# RTU_B2_Power_Supply_Buck_Boost_Regulator.net
KiCad netlist of a schematic drawn in Altium Designer
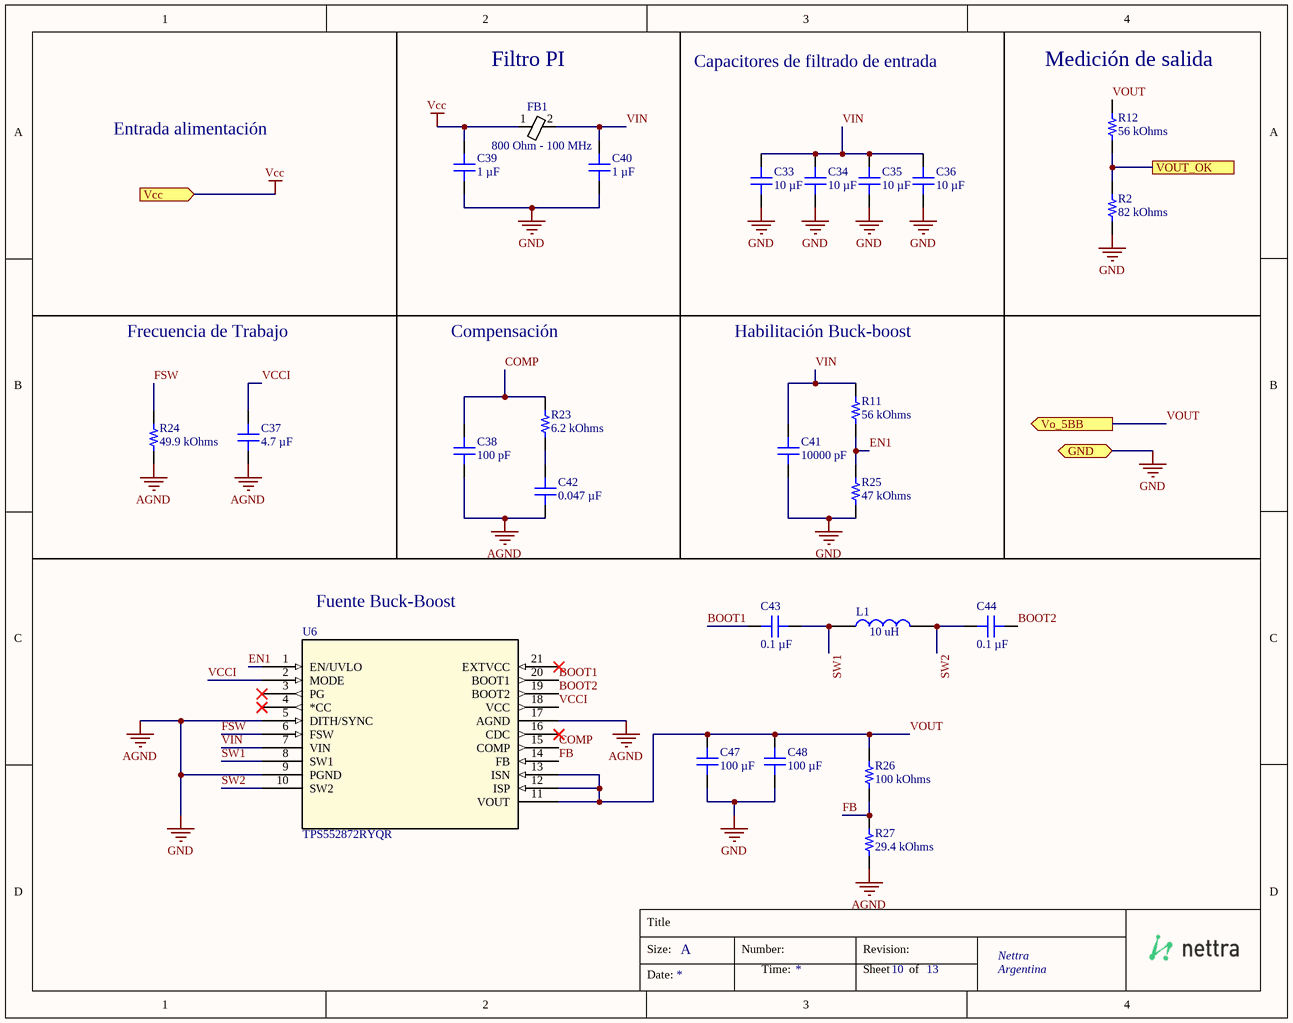
[diagram p0: RTU_B2_Power_Supply_Buck_Boost_Regulator.SchDoc]

(export (version "E")
  (design (tool "Eeschema 10.0.6"))
  (components
    (comp (ref "C33")
      (value "10 µF")
      (footprint "CAP 1210_3225 - 1MM")
      (description "CAP CER 10UF 50V X7S 1210")
      (fields
        (field (name "PART NUMBER") "GCJ32EC71H106KA01L")
        (field (name "MANUFACTURER") "Murata Electronics")
      )
      (libsource (lib "Celestial Altium Library - altium_library") (part "Capacitor"))
    )
    (comp (ref "C34")
      (value "10 µF")
      (footprint "CAP 1210_3225 - 1MM")
      (description "CAP CER 10UF 50V X7S 1210")
      (fields
        (field (name "PART NUMBER") "GCJ32EC71H106KA01L")
        (field (name "MANUFACTURER") "Murata Electronics")
      )
      (libsource (lib "Celestial Altium Library - altium_library") (part "Capacitor"))
    )
    (comp (ref "C35")
      (value "10 µF")
      (footprint "CAP 1210_3225 - 1MM")
      (description "CAP CER 10UF 50V X7S 1210")
      (fields
        (field (name "PART NUMBER") "GCJ32EC71H106KA01L")
        (field (name "MANUFACTURER") "Murata Electronics")
      )
      (libsource (lib "Celestial Altium Library - altium_library") (part "Capacitor"))
    )
    (comp (ref "C36")
      (value "10 µF")
      (footprint "CAP 1210_3225 - 1MM")
      (description "CAP CER 10UF 50V X7S 1210")
      (fields
        (field (name "PART NUMBER") "GCJ32EC71H106KA01L")
        (field (name "MANUFACTURER") "Murata Electronics")
      )
      (libsource (lib "Celestial Altium Library - altium_library") (part "Capacitor"))
    )
    (comp (ref "C37")
      (value "4.7 µF")
      (footprint "MURATA GRM188 0603_1608")
      (description "CAP CER 4.7UF 16V X5R 0603")
      (fields
        (field (name "PART NUMBER") "GRM188R61C475KE11D")
        (field (name "CAPACITANCE") "4.7 µF")
        (field (name "MANUFACTURER") "Murata Electronics")
      )
      (libsource (lib "Celestial Altium Library - altium_library") (part "Capacitor"))
    )
    (comp (ref "C38")
      (value "100 pF")
      (footprint "CAP 0603_1608")
      (description "CAP CER 100PF 50V X7R 0603")
      (fields
        (field (name "PART NUMBER") "CL10B101KB8NFNC")
        (field (name "CAPACITANCE") "100 pF")
        (field (name "MANUFACTURER") "Samsung Electro-Mechanics")
      )
      (libsource (lib "Celestial Altium Library - altium_library") (part "Capacitor"))
    )
    (comp (ref "C39")
      (value "1 µF")
      (footprint "MURATA GRM21B 0805_2012")
      (description "CAP CER 1UF 100V X7S 0805")
      (fields
        (field (name "PART NUMBER") "GRM21BC72A105KE01L")
        (field (name "CAPACITANCE") "1 µF")
        (field (name "MANUFACTURER") "Murata Electronics")
      )
      (libsource (lib "Celestial Altium Library - altium_library") (part "Capacitor"))
    )
    (comp (ref "C40")
      (value "1 µF")
      (footprint "MURATA GRM21B 0805_2012")
      (description "CAP CER 1UF 100V X7S 0805")
      (fields
        (field (name "PART NUMBER") "GRM21BC72A105KE01L")
        (field (name "CAPACITANCE") "1 µF")
        (field (name "MANUFACTURER") "Murata Electronics")
      )
      (libsource (lib "Celestial Altium Library - altium_library") (part "Capacitor"))
    )
    (comp (ref "C41")
      (value "10000 pF")
      (footprint "CAP 0603_1608")
      (description "CAP CER 0603 10NF 16V X7R 10%")
      (fields
        (field (name "PART NUMBER") "C0603C103K4REC7867")
        (field (name "CAPACITANCE") "10000 pF")
        (field (name "MANUFACTURER") "KEMET")
      )
      (libsource (lib "Celestial Altium Library - altium_library") (part "Capacitor"))
    )
    (comp (ref "C42")
      (value "0.047 µF")
      (footprint "CAP 0603_1608")
      (description "CAP CER 0.047UF 100V X7R 0603")
      (fields (field (name "PART NUMBER") "885012206118") (field (name "MANUFACTURER") "Würth Elektronik"))
      (libsource (lib "Celestial Altium Library - altium_library") (part "Capacitor"))
    )
    (comp (ref "C43")
      (value "0.1 µF")
      (footprint "CAP 0402_1005")
      (description "CAP CER 0.1UF 50V X5R 0402")
      (fields
        (field (name "PART NUMBER") "CGA2B3X5R1H104M050BB")
        (field (name "CAPACITANCE") "0.1 µF")
        (field (name "MANUFACTURER") "TDK Corporation")
      )
      (libsource (lib "Celestial Altium Library - altium_library") (part "Capacitor"))
    )
    (comp (ref "C44")
      (value "0.1 µF")
      (footprint "CAP 0402_1005")
      (description "CAP CER 0.1UF 50V X5R 0402")
      (fields
        (field (name "PART NUMBER") "CGA2B3X5R1H104M050BB")
        (field (name "CAPACITANCE") "0.1 µF")
        (field (name "MANUFACTURER") "TDK Corporation")
      )
      (libsource (lib "Celestial Altium Library - altium_library") (part "Capacitor"))
    )
    (comp (ref "C47")
      (value "100 µF")
      (footprint "CAP 1210_3225 - 1MM")
      (description "CAP CER 100UF 16V X5R 1210")
      (fields (field (name "PART NUMBER") "EMK325ABJ107MM-P") (field (name "MANUFACTURER") "Taiyo Yuden"))
      (libsource (lib "Celestial Altium Library - altium_library") (part "Capacitor"))
    )
    (comp (ref "C48")
      (value "100 µF")
      (footprint "CAP 1210_3225 - 1MM")
      (description "CAP CER 100UF 16V X5R 1210")
      (fields (field (name "PART NUMBER") "EMK325ABJ107MM-P") (field (name "MANUFACTURER") "Taiyo Yuden"))
      (libsource (lib "Celestial Altium Library - altium_library") (part "Capacitor"))
    )
    (comp (ref "FB1")
      (value "800 Ohm - 100 MHz")
      (footprint "DIN_DC_Base_Board_components_PCB_footprints:BEADC5651X385N")
      (description "Ferrite Bead")
      (fields
        (field (name "MANUFACTURER_PART_NUMBER") "7427928801")
        (field (name "MOUSER PART NUMBER") "710-7427928801")
      )
      (libsource (lib "DIN_DC_Base_Board_components") (part "Ferrite bead"))
    )
    (comp (ref "L1")
      (value "10 uH")
      (footprint "DIN_DC_Base_Board_components_PCB_footprints:SRP1038A-100M  - Inductor SMD blindado")
      (description "Inductor - 10 uH - 7.5 A")
      (fields
        (field (name "MANUFACTURER_PART_NUMBER") "SRP1038A-100M")
        (field (name "MOUSER PART NUMBER") "652-SRP1038A-100M")
      )
      (libsource (lib "DIN_DC_Base_Board_components") (part "SRP1038A-100M"))
    )
    (comp (ref "R2")
      (value "82 kOhms")
      (footprint "YAGEO RES 0402_1005")
      (description "RES 82K OHM 1% 1/16W 0402")
      (fields (field (name "PART NUMBER") "RC0402FR-0782KL") (field (name "MANUFACTURER") "Yageo"))
      (libsource (lib "Celestial Altium Library - altium_library") (part "Resistor"))
    )
    (comp (ref "R11")
      (value "56 kOhms")
      (footprint "YAGEO RES 0603_1608")
      (description "RES SMD 56K OHM 0.1% 1/10W 0603")
      (fields (field (name "PART NUMBER") "RT0603BRD0756KL") (field (name "MANUFACTURER") "Yageo"))
      (libsource (lib "Celestial Altium Library - altium_library") (part "Resistor"))
    )
    (comp (ref "R12")
      (value "56 kOhms")
      (footprint "YAGEO RES 0402_1005")
      (description "RES 56K OHM 1% 1/16W 0402")
      (fields (field (name "PART NUMBER") "RC0402FR-0756KL") (field (name "MANUFACTURER") "Yageo"))
      (libsource (lib "Celestial Altium Library - altium_library") (part "Resistor"))
    )
    (comp (ref "R23")
      (value "6.2 kOhms")
      (footprint "RES 0603_1608")
      (description "RES 6.2K OHM 0.1% 1/10W 0603")
      (fields (field (name "PART NUMBER") "TNPW06036K20BEEA") (field (name "MANUFACTURER") "Vishay Dale"))
      (libsource (lib "Celestial Altium Library - altium_library") (part "Resistor"))
    )
    (comp (ref "R24")
      (value "49.9 kOhms")
      (footprint "RES 0603_1608")
      (description "RES SMD 49.9K OHM 1% 1/10W 0603")
      (fields (field (name "PART NUMBER") "RCA060349K9FKEA") (field (name "MANUFACTURER") "Vishay Dale"))
      (libsource (lib "Celestial Altium Library - altium_library") (part "Resistor"))
    )
    (comp (ref "R25")
      (value "47 kOhms")
      (footprint "YAGEO RES 0603_1608")
      (description "RES SMD 47K OHM 1% 1/10W 0603")
      (fields (field (name "PART NUMBER") "RT0603FRE0747KL") (field (name "MANUFACTURER") "Yageo"))
      (libsource (lib "Celestial Altium Library - altium_library") (part "Resistor"))
    )
    (comp (ref "R26")
      (value "100 kOhms")
      (footprint "RES 0603_1608")
      (description "RES 100K OHM 0.1% 1/16W 0603")
      (fields
        (field (name "PART NUMBER") "RNCS0603BKE100K")
        (field (name "MANUFACTURER") "Stackpole Electronics Inc")
      )
      (libsource (lib "Celestial Altium Library - altium_library") (part "Resistor"))
    )
    (comp (ref "R27")
      (value "29.4 kOhms")
      (footprint "YAGEO RES 0603_1608")
      (description "RES SMD 29.4KOHM 0.1% 1/10W 0603")
      (fields (field (name "PART NUMBER") "RT0603BRE0729K4L") (field (name "MANUFACTURER") "Yageo"))
      (libsource (lib "Celestial Altium Library - altium_library") (part "Resistor"))
    )
    (comp (ref "U6")
      (value "TPS552872RYQR")
      (footprint "VQFN21_RYQ_TEX")
      (description "36-V, 4-A fully integrated buck-boost converter 21-VQFN-HR -40 to 125")
      (fields (field (name "COPYRIGHT") "Copyright (C) 2025 Ultra Librarian. All rights reserved."))
      (libsource (lib "TPS552872RYQR") (part "TPS552872RYQR"))
    )
  )
  (nets
    (net (code "1") (name "/BOOT1") (class "Default")
      (node (ref "C43") (pin "1") (pinfunction "1_1") (pintype "passive"))
      (node (ref "U6") (pin "20") (pinfunction "BOOT1_20") (pintype "output"))
    )
    (net (code "2") (name "/BOOT2") (class "Default")
      (node (ref "C44") (pin "2") (pinfunction "2_2") (pintype "passive"))
      (node (ref "U6") (pin "19") (pinfunction "BOOT2_19") (pintype "output"))
    )
    (net (code "3") (name "/COMP") (class "Default")
      (node (ref "C38") (pin "2") (pinfunction "2_2") (pintype "passive"))
      (node (ref "R23") (pin "2") (pinfunction "2_2") (pintype "passive"))
      (node (ref "U6") (pin "15") (pinfunction "COMP_15") (pintype "output"))
    )
    (net (code "4") (name "/EN1") (class "Default")
      (node (ref "R11") (pin "1") (pinfunction "1_1") (pintype "passive"))
      (node (ref "R25") (pin "2") (pinfunction "2_2") (pintype "passive"))
      (node (ref "U6") (pin "1") (pinfunction "EN/UVLO_1") (pintype "input"))
    )
    (net (code "5") (name "/FB") (class "Default")
      (node (ref "R26") (pin "1") (pinfunction "1_1") (pintype "passive"))
      (node (ref "R27") (pin "2") (pinfunction "2_2") (pintype "passive"))
      (node (ref "U6") (pin "14") (pinfunction "FB_14") (pintype "input"))
    )
    (net (code "6") (name "/FSW") (class "Default")
      (node (ref "R24") (pin "2") (pinfunction "2_2") (pintype "passive"))
      (node (ref "U6") (pin "6") (pinfunction "FSW_6") (pintype "input"))
    )
    (net (code "7") (name "/SW1") (class "Default")
      (node (ref "C43") (pin "2") (pinfunction "2_2") (pintype "passive"))
      (node (ref "L1") (pin "1") (pinfunction "1_1") (pintype "passive"))
      (node (ref "U6") (pin "8") (pinfunction "SW1_8") (pintype "power_in"))
    )
    (net (code "8") (name "/SW2") (class "Default")
      (node (ref "C44") (pin "1") (pinfunction "1_1") (pintype "passive"))
      (node (ref "L1") (pin "2") (pinfunction "2_2") (pintype "passive"))
      (node (ref "U6") (pin "10") (pinfunction "SW2_10") (pintype "power_in"))
    )
    (net (code "9") (name "/VCCI") (class "Default")
      (node (ref "C37") (pin "2") (pinfunction "2_2") (pintype "passive"))
      (node (ref "U6") (pin "18") (pinfunction "VCC_18") (pintype "output"))
      (node (ref "U6") (pin "2") (pinfunction "MODE_2") (pintype "input"))
    )
    (net (code "10") (name "/VIN") (class "Default")
      (node (ref "C33") (pin "2") (pinfunction "2_2") (pintype "passive"))
      (node (ref "C34") (pin "2") (pinfunction "2_2") (pintype "passive"))
      (node (ref "C35") (pin "2") (pinfunction "2_2") (pintype "passive"))
      (node (ref "C36") (pin "2") (pinfunction "2_2") (pintype "passive"))
      (node (ref "C40") (pin "2") (pinfunction "2_2") (pintype "passive"))
      (node (ref "C41") (pin "2") (pinfunction "2_2") (pintype "passive"))
      (node (ref "FB1") (pin "2") (pinfunction "1_2") (pintype "passive"))
      (node (ref "R11") (pin "2") (pinfunction "2_2") (pintype "passive"))
      (node (ref "U6") (pin "7") (pinfunction "VIN_7") (pintype "power_in"))
    )
    (net (code "11") (name "/VOUT") (class "Default")
      (node (ref "C47") (pin "1") (pinfunction "1_1") (pintype "passive"))
      (node (ref "C48") (pin "1") (pinfunction "1_1") (pintype "passive"))
      (node (ref "R12") (pin "2") (pinfunction "2_2") (pintype "passive"))
      (node (ref "R26") (pin "2") (pinfunction "2_2") (pintype "passive"))
      (node (ref "U6") (pin "11") (pinfunction "VOUT_11") (pintype "power_in"))
      (node (ref "U6") (pin "12") (pinfunction "ISP_12") (pintype "input"))
      (node (ref "U6") (pin "13") (pinfunction "ISN_13") (pintype "input"))
    )
    (net (code "12") (name "/VOUT_OK") (class "Default")
      (node (ref "R12") (pin "1") (pinfunction "1_1") (pintype "passive"))
      (node (ref "R2") (pin "2") (pinfunction "2_2") (pintype "passive"))
    )
    (net (code "13") (name "AGND") (class "Default")
      (node (ref "C33") (pin "1") (pinfunction "1_1") (pintype "passive"))
      (node (ref "C34") (pin "1") (pinfunction "1_1") (pintype "passive"))
      (node (ref "C35") (pin "1") (pinfunction "1_1") (pintype "passive"))
      (node (ref "C36") (pin "1") (pinfunction "1_1") (pintype "passive"))
      (node (ref "C37") (pin "1") (pinfunction "1_1") (pintype "passive"))
      (node (ref "C38") (pin "1") (pinfunction "1_1") (pintype "passive"))
      (node (ref "C39") (pin "1") (pinfunction "1_1") (pintype "passive"))
      (node (ref "C40") (pin "1") (pinfunction "1_1") (pintype "passive"))
      (node (ref "C41") (pin "1") (pinfunction "1_1") (pintype "passive"))
      (node (ref "C42") (pin "1") (pinfunction "1_1") (pintype "passive"))
      (node (ref "C47") (pin "2") (pinfunction "2_2") (pintype "passive"))
      (node (ref "C48") (pin "2") (pinfunction "2_2") (pintype "passive"))
      (node (ref "R2") (pin "1") (pinfunction "1_1") (pintype "passive"))
      (node (ref "R24") (pin "1") (pinfunction "1_1") (pintype "passive"))
      (node (ref "R25") (pin "1") (pinfunction "1_1") (pintype "passive"))
      (node (ref "R27") (pin "1") (pinfunction "1_1") (pintype "passive"))
      (node (ref "U6") (pin "17") (pinfunction "AGND_17") (pintype "power_in"))
      (node (ref "U6") (pin "5") (pinfunction "DITH/SYNC_5") (pintype "input"))
      (node (ref "U6") (pin "9") (pinfunction "PGND_9") (pintype "power_in"))
    )
    (net (code "14") (name "Net-(C42-Pad2)") (class "Default")
      (node (ref "C42") (pin "2") (pinfunction "2_2") (pintype "passive"))
      (node (ref "R23") (pin "1") (pinfunction "1_1") (pintype "passive"))
    )
    (net (code "15") (name "Vcc") (class "Default")
      (node (ref "C39") (pin "2") (pinfunction "2_2") (pintype "passive"))
      (node (ref "FB1") (pin "1") (pinfunction "1_1") (pintype "passive"))
    )
    (net (code "16") (name "unconnected-(U6-*CC-Pad4)") (class "Default")
      (node (ref "U6") (pin "4") (pinfunction "*CC_4") (pintype "output+no_connect"))
    )
    (net (code "17") (name "unconnected-(U6-CDC-Pad16)") (class "Default")
      (node (ref "U6") (pin "16") (pinfunction "CDC_16") (pintype "output+no_connect"))
    )
    (net (code "18") (name "unconnected-(U6-EXTVCC-Pad21)") (class "Default")
      (node (ref "U6") (pin "21") (pinfunction "EXTVCC_21") (pintype "input+no_connect"))
    )
    (net (code "19") (name "unconnected-(U6-PG-Pad3)") (class "Default")
      (node (ref "U6") (pin "3") (pinfunction "PG_3") (pintype "output+no_connect"))
    )
  )
)
